# 1_Board_schdoc.net
KiCad netlist of a schematic drawn in Altium Designer
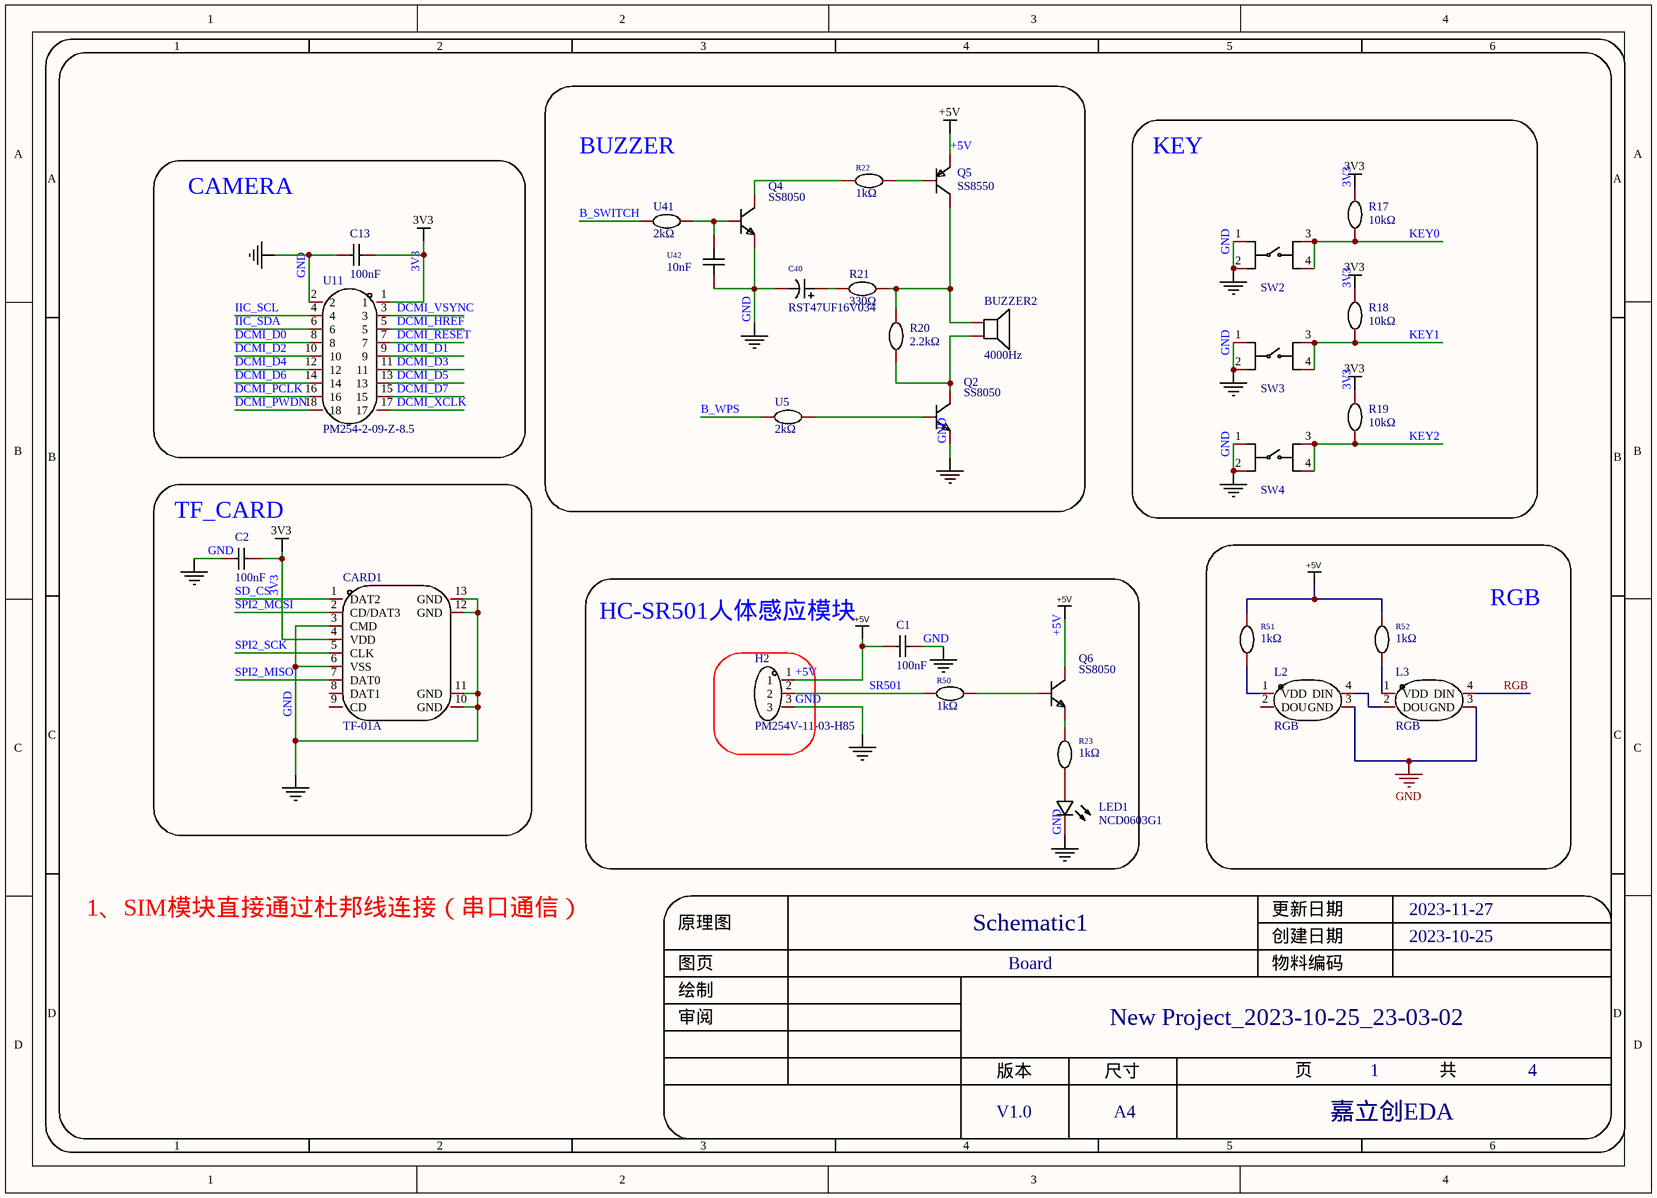
[diagram p0: 1_Board.schdoc.schdoc]

(export (version "E")
  (design (tool "Eeschema 10.0.6"))
  (components
    (comp (ref "BUZZER2")
      (value "4000Hz")
      (footprint "BUZ-TH_BD14.0-P7.60-D0.7-FD")
      (fields
        (field (name "NAME") "4000Hz")
        (field (name "MANUFACTURER") "S&amp;S(海旭)")
        (field (name "MANUFACTURER PART") "SFN-1407PA7.6")
      )
      (libsource (lib "altium-import") (part "root_0_SFN-1407PA7.6_"))
    )
    (comp (ref "C1")
      (value "100nF")
      (footprint "C0603")
      (description "容值:100nF;精度:±10%;额定电压:50V;材质(温度系数):X7R;")
      (fields
        (field (name "NAME") "100nF")
        (field (name "MANUFACTURER") "FH(风华)")
        (field (name "MANUFACTURER PART") "0603B104K500NT")
      )
      (libsource (lib "altium-import") (part "root_0_mirrored_0603B104K500NT_"))
    )
    (comp (ref "C2")
      (value "100nF")
      (footprint "C0603")
      (description "容值:100nF;精度:±10%;额定电压:50V;材质(温度系数):X7R;")
      (fields
        (field (name "NAME") "100nF")
        (field (name "MANUFACTURER") "FH(风华)")
        (field (name "MANUFACTURER PART") "0603B104K500NT")
      )
      (libsource (lib "altium-import") (part "root_0_0603B104K500NT_"))
    )
    (comp (ref "C13")
      (value "100nF")
      (footprint "C0603")
      (description "容值:100nF;精度:±10%;额定电压:50V;材质(温度系数):X7R;")
      (fields
        (field (name "NAME") "100nF")
        (field (name "MANUFACTURER") "FH(风华)")
        (field (name "MANUFACTURER PART") "0603B104K500NT")
      )
      (libsource (lib "altium-import") (part "root_0_0603B104K500NT_"))
    )
    (comp (ref "C40")
      (value "RST47UF16V034")
      (footprint "CAP-SMD_BD5.0-L5.3-W5.3-LS6.0-FD")
      (description "RST宽温通用品 105℃2000小时 等同RVT VT XT系列贴片电解电容")
      (fields (field (name "NAME") "RST47UF16V034") (field (name "MANUFACTURER") "KNSCHA(科尼盛)"))
      (libsource (lib "altium-import") (part "root_2_RST47UF16V034_"))
    )
    (comp (ref "CARD1")
      (value "TF-01A")
      (footprint "TF-SMD_TF-02")
      (description "卡类型:MicroSD卡(TF卡);连接器类型:卡座;卡连接方式:自弹式;本体最大高度:2mm;工作温度范围:-;")
      (fields (field (name "NAME") "TF-01A") (field (name "MANUFACTURER") "Yuandi(元迪)"))
      (libsource (lib "altium-import") (part "root_0_TF-01A_C2889258_"))
    )
    (comp (ref "H2")
      (value "PM254V-11-03-H85")
      (footprint "HDR-TH_3P-P2.54-V-F")
      (description "排数:单排;总孔位数:3P;间距:2.54mm;插孔结构:1x3P;行距:-;安装类型:直插;塑高:-;触头材质:黄铜;触头镀层:-;")
      (fields (field (name "NAME") "PM254V-11-03-H85") (field (name "MANUFACTURER") "XFCN(兴飞)"))
      (libsource (lib "altium-import") (part "root_0_mirrored_PM254V-11-03-H85_"))
    )
    (comp (ref "L2") (value "RGB") (footprint "RGB") (libsource (lib "int_lock") (part "RGB")))
    (comp (ref "L3") (value "RGB") (footprint "RGB") (libsource (lib "int_lock") (part "RGB")))
    (comp (ref "LED1")
      (value "NCD0603G1")
      (footprint "LED0603-RD")
      (description "发光颜色:翠绿色;功率:72mW;透镜颜色:无色透明;主波长:515nm~530nm;发光强度:330mcd~900mcd;发光角度:130°;工作温度:-30℃~+85℃;")
      (fields (field (name "NAME") "NCD0603G1") (field (name "MANUFACTURER") "国星光电"))
      (libsource (lib "altium-import") (part "root_3_NCD0603G1_"))
    )
    (comp (ref "Q2")
      (value "SS8050")
      (footprint "SOT-23-3_L2.9-W1.3-P1.90-LS2.4-BR")
      (description "直流电流增益(hFE@Ic,Vce):200@100mA,1V;功率(Pd):300mW;集射极击穿电压(Vceo):25V;集电极电流(Ic):1.5A;晶体管类型:NPN;")
      (fields (field (name "NAME") "SS8050") (field (name "MANUFACTURER") "CJ(江苏长电/长晶)"))
      (libsource (lib "altium-import") (part "root_0_SS8050_C2150_"))
    )
    (comp (ref "Q4")
      (value "SS8050")
      (footprint "SOT-23-3_L2.9-W1.3-P1.90-LS2.4-BR")
      (description "直流电流增益(hFE@Ic,Vce):200@100mA,1V;功率(Pd):300mW;集射极击穿电压(Vceo):25V;集电极电流(Ic):1.5A;晶体管类型:NPN;")
      (fields (field (name "NAME") "SS8050") (field (name "MANUFACTURER") "CJ(江苏长电/长晶)"))
      (libsource (lib "altium-import") (part "root_0_SS8050_C2150_"))
    )
    (comp (ref "Q5")
      (value "SS8550")
      (footprint "SOT-23-3_L2.9-W1.3-P1.90-LS2.4-BR")
      (fields (field (name "NAME") "SS8550") (field (name "MANUFACTURER") "Doeshare(德芯)"))
      (libsource (lib "altium-import") (part "root_2_mirrored_SS8550_"))
    )
    (comp (ref "Q6")
      (value "SS8050")
      (footprint "SOT-23-3_L2.9-W1.3-P1.90-LS2.4-BR")
      (description "直流电流增益(hFE@Ic,Vce):200@100mA,1V;功率(Pd):300mW;集射极击穿电压(Vceo):25V;集电极电流(Ic):1.5A;晶体管类型:NPN;")
      (fields (field (name "NAME") "SS8050") (field (name "MANUFACTURER") "CJ(江苏长电/长晶)"))
      (libsource (lib "altium-import") (part "root_0_SS8050_C2150_"))
    )
    (comp (ref "R17")
      (value "10kΩ")
      (footprint "R0603")
      (description "阻值:10kΩ;精度:±5%;")
      (fields
        (field (name "NAME") "10kΩ")
        (field (name "MANUFACTURER") "VO(翔胜)")
        (field (name "MANUFACTURER PART") "SCR0603J10K")
      )
      (libsource (lib "altium-import") (part "root_1_SCR0603J10K_"))
    )
    (comp (ref "R18")
      (value "10kΩ")
      (footprint "R0603")
      (description "阻值:10kΩ;精度:±5%;")
      (fields
        (field (name "NAME") "10kΩ")
        (field (name "MANUFACTURER") "VO(翔胜)")
        (field (name "MANUFACTURER PART") "SCR0603J10K")
      )
      (libsource (lib "altium-import") (part "root_1_SCR0603J10K_"))
    )
    (comp (ref "R19")
      (value "10kΩ")
      (footprint "R0603")
      (description "阻值:10kΩ;精度:±5%;")
      (fields
        (field (name "NAME") "10kΩ")
        (field (name "MANUFACTURER") "VO(翔胜)")
        (field (name "MANUFACTURER PART") "SCR0603J10K")
      )
      (libsource (lib "altium-import") (part "root_1_SCR0603J10K_"))
    )
    (comp (ref "R20")
      (value "2.2kΩ")
      (footprint "R0603")
      (description "阻值:2.2kΩ;精度:±5%;")
      (fields
        (field (name "NAME") "2.2kΩ")
        (field (name "MANUFACTURER") "VO(翔胜)")
        (field (name "MANUFACTURER PART") "SCR0603J2K2")
      )
      (libsource (lib "altium-import") (part "root_1_SCR0603J2K2_"))
    )
    (comp (ref "R21")
      (value "330Ω")
      (footprint "R0603")
      (description "阻值:330Ω;精度:±0.1%;功率:100mW;温度系数:±25ppm/℃;电阻类型:薄膜电阻;")
      (fields
        (field (name "NAME") "330Ω")
        (field (name "MANUFACTURER") "UNI-ROYAL(厚声)")
        (field (name "MANUFACTURER PART") "TC0325B3300T5F")
      )
      (libsource (lib "altium-import") (part "root_0_TC0325B3300T5F_"))
    )
    (comp (ref "R22")
      (value "1kΩ")
      (footprint "R0603")
      (description "阻值:1kΩ;精度:±1%;")
      (fields
        (field (name "NAME") "1kΩ")
        (field (name "MANUFACTURER") "VO(翔胜)")
        (field (name "MANUFACTURER PART") "SCR0603F1K")
      )
      (libsource (lib "altium-import") (part "root_0_SCR0603F1K_"))
    )
    (comp (ref "R23")
      (value "1kΩ")
      (footprint "R0603")
      (description "阻值:1kΩ;精度:±1%;")
      (fields
        (field (name "NAME") "1kΩ")
        (field (name "MANUFACTURER") "VO(翔胜)")
        (field (name "MANUFACTURER PART") "SCR0603F1K")
      )
      (libsource (lib "altium-import") (part "root_1_SCR0603F1K_"))
    )
    (comp (ref "R50")
      (value "1kΩ")
      (footprint "R0603")
      (description "阻值:1kΩ;精度:±1%;")
      (fields
        (field (name "NAME") "1kΩ")
        (field (name "MANUFACTURER") "VO(翔胜)")
        (field (name "MANUFACTURER PART") "SCR0603F1K")
      )
      (libsource (lib "altium-import") (part "root_2_SCR0603F1K_"))
    )
    (comp (ref "R51")
      (value "1kΩ")
      (footprint "R0603")
      (description "阻值:1kΩ;精度:±1%;")
      (fields
        (field (name "NAME") "1kΩ")
        (field (name "MANUFACTURER") "VO(翔胜)")
        (field (name "MANUFACTURER PART") "SCR0603F1K")
      )
      (libsource (lib "altium-import") (part "root_1_SCR0603F1K_"))
    )
    (comp (ref "R52")
      (value "1kΩ")
      (footprint "R0603")
      (description "阻值:1kΩ;精度:±1%;")
      (fields
        (field (name "NAME") "1kΩ")
        (field (name "MANUFACTURER") "VO(翔胜)")
        (field (name "MANUFACTURER PART") "SCR0603F1K")
      )
      (libsource (lib "altium-import") (part "root_1_SCR0603F1K_"))
    )
    (comp (ref "SW2")
      (value "K2-6639SP-C4SC-04")
      (footprint "KEY-SMD_4P-L6.0-W6.0-P3.90-LS10.0")
      (fields (field (name "MANUFACTURER") "韩国韩荣"))
      (libsource (lib "altium-import") (part "root_0_K2-6639SP-C4SC-04_"))
    )
    (comp (ref "SW3")
      (value "K2-6639SP-C4SC-04")
      (footprint "KEY-SMD_4P-L6.0-W6.0-P3.90-LS10.0")
      (fields (field (name "MANUFACTURER") "韩国韩荣"))
      (libsource (lib "altium-import") (part "root_0_K2-6639SP-C4SC-04_"))
    )
    (comp (ref "SW4")
      (value "K2-6639SP-C4SC-04")
      (footprint "KEY-SMD_4P-L6.0-W6.0-P3.90-LS10.0")
      (fields (field (name "MANUFACTURER") "韩国韩荣"))
      (libsource (lib "altium-import") (part "root_0_K2-6639SP-C4SC-04_"))
    )
    (comp (ref "U5")
      (value "2kΩ")
      (footprint "R0603")
      (description "阻值:2kΩ;精度:±0.1%;")
      (fields
        (field (name "NAME") "2kΩ")
        (field (name "MANUFACTURER") "RALEC(旺诠)")
        (field (name "MANUFACTURER PART") "RTX032001BETP")
      )
      (libsource (lib "altium-import") (part "root_2_RTX032001BETP_"))
    )
    (comp (ref "U11")
      (value "PM254-2-09-Z-8.5")
      (footprint "HDR-TH_18P-P2.54-V-F-R2-C9-S2.54")
      (fields (field (name "NAME") "PM254-2-09-Z-8.5") (field (name "MANUFACTURER") "HCTL(华灿天禄)"))
      (libsource (lib "altium-import") (part "root_0_mirrored_PM254-2-09-Z-8.5_"))
    )
    (comp (ref "U41")
      (value "2kΩ")
      (footprint "R0603")
      (description "阻值:2kΩ;精度:±0.1%;")
      (fields
        (field (name "NAME") "2kΩ")
        (field (name "MANUFACTURER") "RALEC(旺诠)")
        (field (name "MANUFACTURER PART") "RTX032001BETP")
      )
      (libsource (lib "altium-import") (part "root_2_RTX032001BETP_"))
    )
    (comp (ref "U42")
      (value "10nF")
      (footprint "C0603")
      (description "容值:10nF;精度:±10%;额定电压:100V;材质(温度系数):X8R;")
      (fields
        (field (name "NAME") "10nF")
        (field (name "MANUFACTURER") "TDK")
        (field (name "MANUFACTURER PART") "C1608X8R2A103K080AA")
      )
      (libsource (lib "altium-import") (part "root_1_C1608X8R2A103K080AA_"))
    )
  )
  (nets
    (net (code "1") (name "+5V") (class "Default")
      (node (ref "C1") (pin "2") (pinfunction "2_2") (pintype "passive"))
      (node (ref "H2") (pin "1") (pinfunction "1_1") (pintype "passive"))
      (node (ref "Q5") (pin "2") (pinfunction "E_2") (pintype "passive"))
      (node (ref "Q6") (pin "3") (pinfunction "C_3") (pintype "passive"))
      (node (ref "R51") (pin "2") (pinfunction "2_2") (pintype "passive"))
      (node (ref "R52") (pin "2") (pinfunction "2_2") (pintype "passive"))
    )
    (net (code "2") (name "/B_SWITCH") (class "Default")
      (node (ref "U41") (pin "2") (pinfunction "2_2") (pintype "passive"))
    )
    (net (code "3") (name "/B_WPS") (class "Default")
      (node (ref "U5") (pin "2") (pinfunction "2_2") (pintype "passive"))
    )
    (net (code "4") (name "/DCMI_D0") (class "Default")
      (node (ref "U11") (pin "8") (pinfunction "8_8") (pintype "passive"))
    )
    (net (code "5") (name "/DCMI_D1") (class "Default")
      (node (ref "U11") (pin "9") (pinfunction "9_9") (pintype "passive"))
    )
    (net (code "6") (name "/DCMI_D2") (class "Default")
      (node (ref "U11") (pin "10") (pinfunction "10_10") (pintype "passive"))
    )
    (net (code "7") (name "/DCMI_D3") (class "Default")
      (node (ref "U11") (pin "11") (pinfunction "11_11") (pintype "passive"))
    )
    (net (code "8") (name "/DCMI_D4") (class "Default")
      (node (ref "U11") (pin "12") (pinfunction "12_12") (pintype "passive"))
    )
    (net (code "9") (name "/DCMI_D5") (class "Default")
      (node (ref "U11") (pin "13") (pinfunction "13_13") (pintype "passive"))
    )
    (net (code "10") (name "/DCMI_D6") (class "Default")
      (node (ref "U11") (pin "14") (pinfunction "14_14") (pintype "passive"))
    )
    (net (code "11") (name "/DCMI_D7") (class "Default")
      (node (ref "U11") (pin "15") (pinfunction "15_15") (pintype "passive"))
    )
    (net (code "12") (name "/DCMI_HREF") (class "Default")
      (node (ref "U11") (pin "5") (pinfunction "5_5") (pintype "passive"))
    )
    (net (code "13") (name "/DCMI_PCLK") (class "Default")
      (node (ref "U11") (pin "16") (pinfunction "16_16") (pintype "passive"))
    )
    (net (code "14") (name "/DCMI_PWDN") (class "Default")
      (node (ref "U11") (pin "18") (pinfunction "18_18") (pintype "passive"))
    )
    (net (code "15") (name "/DCMI_RESET") (class "Default")
      (node (ref "U11") (pin "7") (pinfunction "7_7") (pintype "passive"))
    )
    (net (code "16") (name "/DCMI_VSYNC") (class "Default")
      (node (ref "U11") (pin "3") (pinfunction "3_3") (pintype "passive"))
    )
    (net (code "17") (name "/DCMI_XCLK") (class "Default")
      (node (ref "U11") (pin "17") (pinfunction "17_17") (pintype "passive"))
    )
    (net (code "18") (name "/IIC_SCL") (class "Default")
      (node (ref "U11") (pin "4") (pinfunction "4_4") (pintype "passive"))
    )
    (net (code "19") (name "/IIC_SDA") (class "Default")
      (node (ref "U11") (pin "6") (pinfunction "6_6") (pintype "passive"))
    )
    (net (code "20") (name "/KEY0") (class "Default")
      (node (ref "R17") (pin "1") (pinfunction "1_1") (pintype "passive"))
      (node (ref "SW2") (pin "3") (pinfunction "3_3") (pintype "passive"))
      (node (ref "SW2") (pin "4") (pinfunction "4_4") (pintype "passive"))
    )
    (net (code "21") (name "/KEY1") (class "Default")
      (node (ref "R18") (pin "1") (pinfunction "1_1") (pintype "passive"))
      (node (ref "SW3") (pin "3") (pinfunction "3_3") (pintype "passive"))
      (node (ref "SW3") (pin "4") (pinfunction "4_4") (pintype "passive"))
    )
    (net (code "22") (name "/KEY2") (class "Default")
      (node (ref "R19") (pin "1") (pinfunction "1_1") (pintype "passive"))
      (node (ref "SW4") (pin "3") (pinfunction "3_3") (pintype "passive"))
      (node (ref "SW4") (pin "4") (pinfunction "4_4") (pintype "passive"))
    )
    (net (code "23") (name "/RGB") (class "Default")
      (node (ref "L3") (pin "4") (pinfunction "DIN_4") (pintype "passive"))
    )
    (net (code "24") (name "/SD_CS") (class "Default")
      (node (ref "CARD1") (pin "1") (pinfunction "DAT2_1") (pintype "passive"))
    )
    (net (code "25") (name "/SPI2_MISO") (class "Default")
      (node (ref "CARD1") (pin "7") (pinfunction "DAT0_7") (pintype "passive"))
    )
    (net (code "26") (name "/SPI2_MOSI") (class "Default")
      (node (ref "CARD1") (pin "2") (pinfunction "CD/DAT3_2") (pintype "passive"))
    )
    (net (code "27") (name "/SPI2_SCK") (class "Default")
      (node (ref "CARD1") (pin "5") (pinfunction "CLK_5") (pintype "passive"))
    )
    (net (code "28") (name "/SR501") (class "Default")
      (node (ref "H2") (pin "2") (pinfunction "2_2") (pintype "passive"))
      (node (ref "R50") (pin "2") (pinfunction "2_2") (pintype "passive"))
    )
    (net (code "29") (name "3V3") (class "Default")
      (node (ref "C13") (pin "2") (pinfunction "2_2") (pintype "passive"))
      (node (ref "C2") (pin "2") (pinfunction "2_2") (pintype "passive"))
      (node (ref "CARD1") (pin "4") (pinfunction "VDD_4") (pintype "passive"))
      (node (ref "R17") (pin "2") (pinfunction "2_2") (pintype "passive"))
      (node (ref "R18") (pin "2") (pinfunction "2_2") (pintype "passive"))
      (node (ref "R19") (pin "2") (pinfunction "2_2") (pintype "passive"))
      (node (ref "U11") (pin "1") (pinfunction "1_1") (pintype "passive"))
    )
    (net (code "30") (name "GND") (class "Default")
      (node (ref "C1") (pin "1") (pinfunction "1_1") (pintype "passive"))
      (node (ref "C13") (pin "1") (pinfunction "1_1") (pintype "passive"))
      (node (ref "C2") (pin "1") (pinfunction "1_1") (pintype "passive"))
      (node (ref "C40") (pin "2") (pinfunction "2_2") (pintype "passive"))
      (node (ref "CARD1") (pin "10") (pinfunction "GND_10") (pintype "passive"))
      (node (ref "CARD1") (pin "11") (pinfunction "GND_11") (pintype "passive"))
      (node (ref "CARD1") (pin "12") (pinfunction "GND_12") (pintype "passive"))
      (node (ref "CARD1") (pin "13") (pinfunction "GND_13") (pintype "passive"))
      (node (ref "CARD1") (pin "3") (pinfunction "CMD_3") (pintype "passive"))
      (node (ref "CARD1") (pin "6") (pinfunction "VSS_6") (pintype "passive"))
      (node (ref "H2") (pin "3") (pinfunction "3_3") (pintype "passive"))
      (node (ref "L2") (pin "3") (pinfunction "GND_3") (pintype "passive"))
      (node (ref "L3") (pin "3") (pinfunction "GND_3") (pintype "passive"))
      (node (ref "LED1") (pin "1") (pinfunction "K_1") (pintype "passive"))
      (node (ref "Q2") (pin "2") (pinfunction "E_2") (pintype "passive"))
      (node (ref "Q4") (pin "2") (pinfunction "E_2") (pintype "passive"))
      (node (ref "SW2") (pin "1") (pinfunction "1_1") (pintype "passive"))
      (node (ref "SW2") (pin "2") (pinfunction "2_2") (pintype "passive"))
      (node (ref "SW3") (pin "1") (pinfunction "1_1") (pintype "passive"))
      (node (ref "SW3") (pin "2") (pinfunction "2_2") (pintype "passive"))
      (node (ref "SW4") (pin "1") (pinfunction "1_1") (pintype "passive"))
      (node (ref "SW4") (pin "2") (pinfunction "2_2") (pintype "passive"))
      (node (ref "U11") (pin "2") (pinfunction "2_2") (pintype "passive"))
      (node (ref "U42") (pin "1") (pinfunction "1_1") (pintype "passive"))
    )
    (net (code "31") (name "Net-(C40-Pad1)") (class "Default")
      (node (ref "C40") (pin "1") (pinfunction "1_1") (pintype "passive"))
      (node (ref "R21") (pin "1") (pinfunction "1_1") (pintype "passive"))
    )
    (net (code "32") (name "Net-(L2-DIN)") (class "Default")
      (node (ref "L2") (pin "4") (pinfunction "DIN_4") (pintype "passive"))
      (node (ref "L3") (pin "2") (pinfunction "DOU_2") (pintype "passive"))
    )
    (net (code "33") (name "Net-(L2-VDD)") (class "Default")
      (node (ref "L2") (pin "1") (pinfunction "VDD_1") (pintype "passive"))
      (node (ref "R51") (pin "1") (pinfunction "1_1") (pintype "passive"))
    )
    (net (code "34") (name "Net-(L3-VDD)") (class "Default")
      (node (ref "L3") (pin "1") (pinfunction "VDD_1") (pintype "passive"))
      (node (ref "R52") (pin "1") (pinfunction "1_1") (pintype "passive"))
    )
    (net (code "35") (name "Net-(LED1-A)") (class "Default")
      (node (ref "LED1") (pin "2") (pinfunction "A_2") (pintype "passive"))
      (node (ref "R23") (pin "1") (pinfunction "1_1") (pintype "passive"))
    )
    (net (code "36") (name "Net-(Q2-B)") (class "Default")
      (node (ref "Q2") (pin "1") (pinfunction "B_1") (pintype "passive"))
      (node (ref "U5") (pin "1") (pinfunction "1_1") (pintype "passive"))
    )
    (net (code "37") (name "Net-(Q2-C)") (class "Default")
      (node (ref "BUZZER2") (pin "2") (pinfunction "2_2") (pintype "passive"))
      (node (ref "Q2") (pin "3") (pinfunction "C_3") (pintype "passive"))
      (node (ref "R20") (pin "1") (pinfunction "1_1") (pintype "passive"))
    )
    (net (code "38") (name "Net-(Q4-B)") (class "Default")
      (node (ref "Q4") (pin "1") (pinfunction "B_1") (pintype "passive"))
      (node (ref "U41") (pin "1") (pinfunction "1_1") (pintype "passive"))
      (node (ref "U42") (pin "2") (pinfunction "2_2") (pintype "passive"))
    )
    (net (code "39") (name "Net-(Q4-C)") (class "Default")
      (node (ref "Q4") (pin "3") (pinfunction "C_3") (pintype "passive"))
      (node (ref "R22") (pin "1") (pinfunction "1_1") (pintype "passive"))
    )
    (net (code "40") (name "Net-(Q5-B)") (class "Default")
      (node (ref "Q5") (pin "1") (pinfunction "B_1") (pintype "passive"))
      (node (ref "R22") (pin "2") (pinfunction "2_2") (pintype "passive"))
    )
    (net (code "41") (name "Net-(Q5-C)") (class "Default")
      (node (ref "BUZZER2") (pin "1") (pinfunction "1_1") (pintype "passive"))
      (node (ref "Q5") (pin "3") (pinfunction "C_3") (pintype "passive"))
      (node (ref "R20") (pin "2") (pinfunction "2_2") (pintype "passive"))
      (node (ref "R21") (pin "2") (pinfunction "2_2") (pintype "passive"))
    )
    (net (code "42") (name "Net-(Q6-B)") (class "Default")
      (node (ref "Q6") (pin "1") (pinfunction "B_1") (pintype "passive"))
      (node (ref "R50") (pin "1") (pinfunction "1_1") (pintype "passive"))
    )
    (net (code "43") (name "Net-(Q6-E)") (class "Default")
      (node (ref "Q6") (pin "2") (pinfunction "E_2") (pintype "passive"))
      (node (ref "R23") (pin "2") (pinfunction "2_2") (pintype "passive"))
    )
    (net (code "44") (name "unconnected-(CARD1-CD-Pad9)") (class "Default")
      (node (ref "CARD1") (pin "9") (pinfunction "CD_9") (pintype "passive"))
    )
    (net (code "45") (name "unconnected-(CARD1-DAT1-Pad8)") (class "Default")
      (node (ref "CARD1") (pin "8") (pinfunction "DAT1_8") (pintype "passive"))
    )
    (net (code "46") (name "unconnected-(L2-DOU-Pad2)") (class "Default")
      (node (ref "L2") (pin "2") (pinfunction "DOU_2") (pintype "passive"))
    )
  )
)
